# DS2482_Breakout.net
KiCad netlist of a schematic drawn in EAGLE
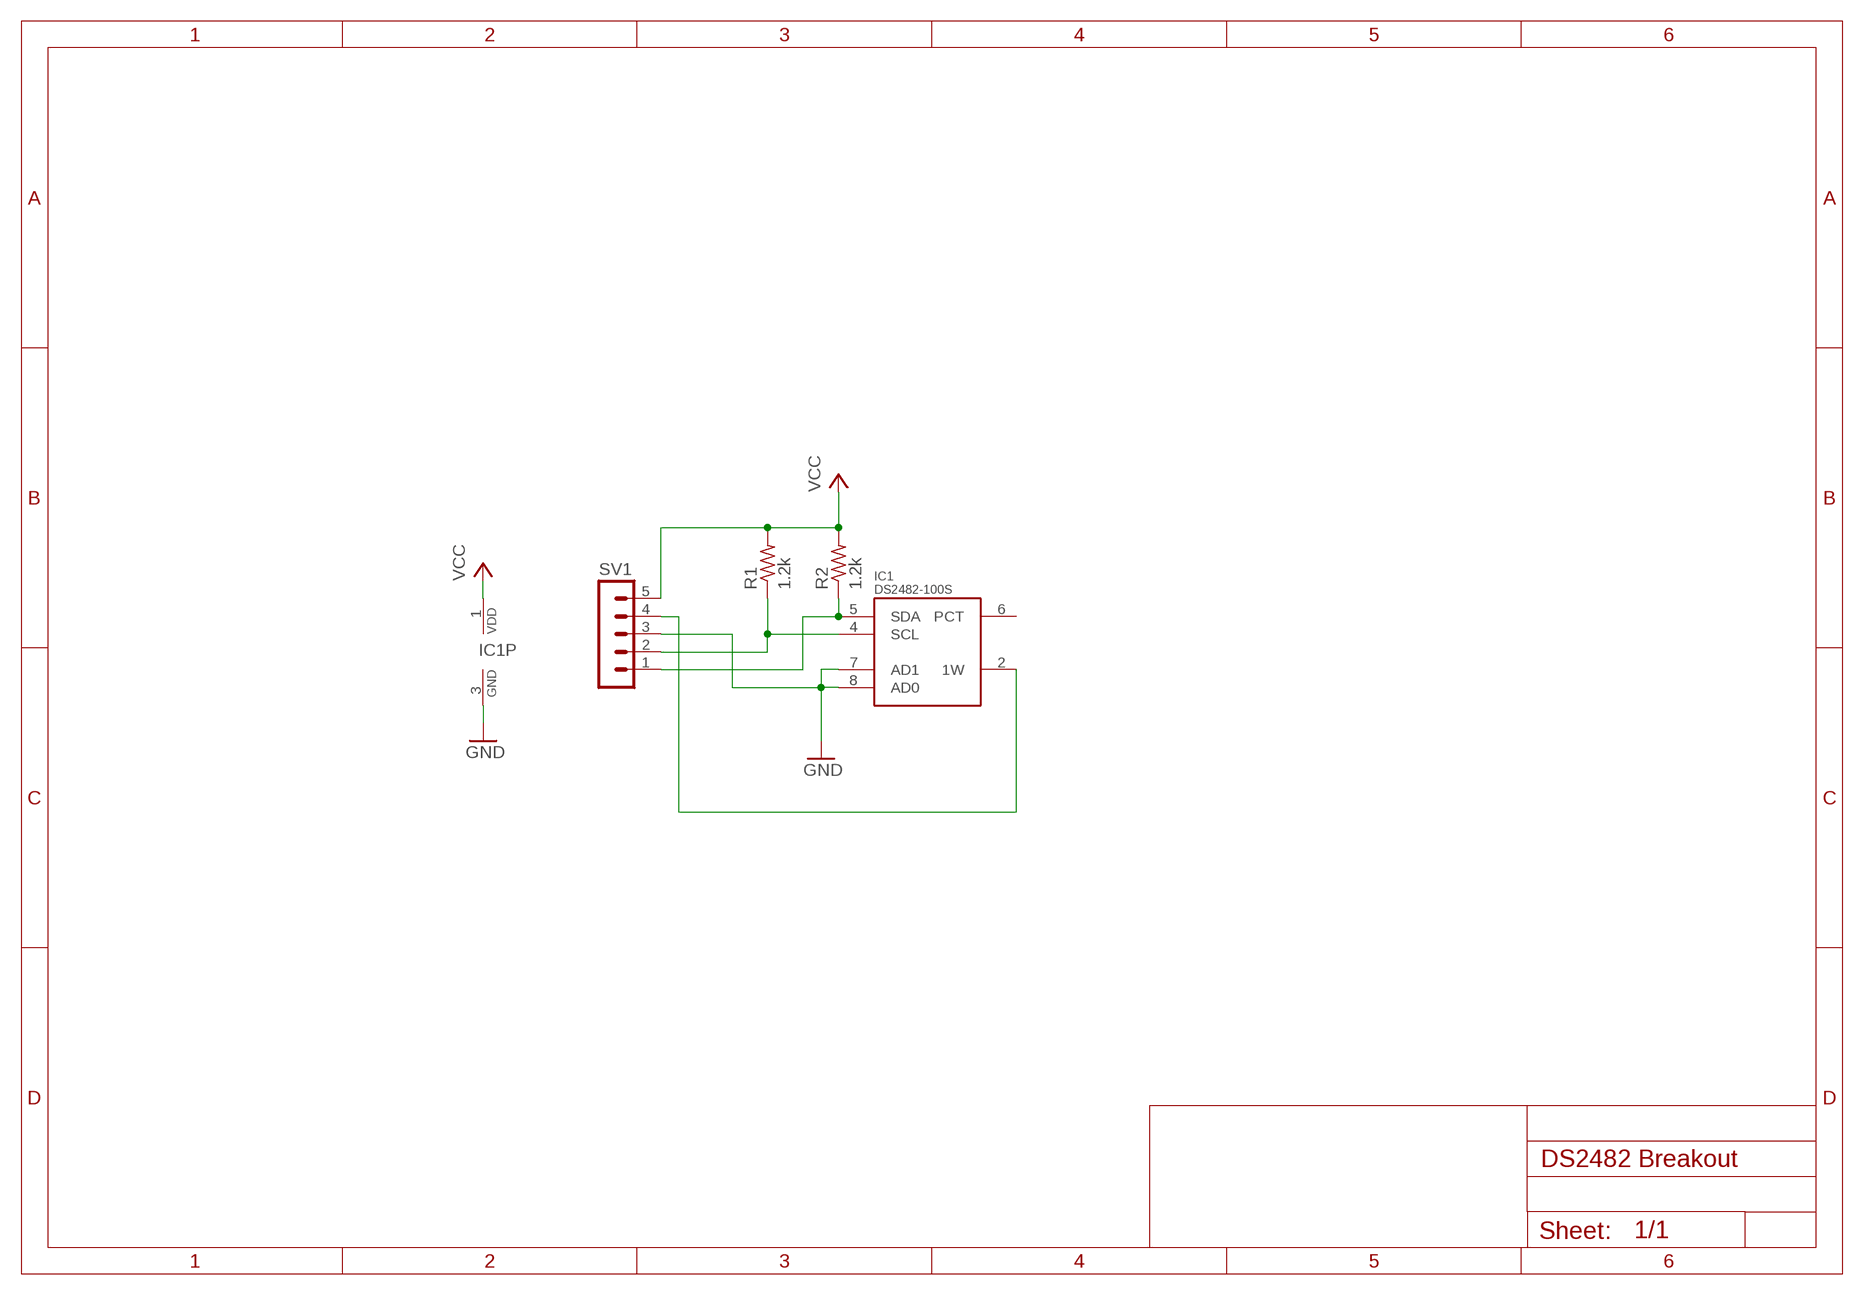
[diagram p0: schematic, sheet 1]

(export (version "E")
  (design (tool "Eeschema 10.0.6"))
  (components
    (comp (ref "IC1")
      (value "DS2482-100S")
      (footprint "eagle-import:SO08")
      (libsource (lib "eagle-import") (part "DS2482-100S"))
    )
    (comp (ref "R1")
      (value "1.2k")
      (footprint "eagle-import:M0805")
      (libsource (lib "eagle-import") (part "R-US_M0805"))
    )
    (comp (ref "R2")
      (value "1.2k")
      (footprint "eagle-import:M0805")
      (libsource (lib "eagle-import") (part "R-US_M0805"))
    )
    (comp (ref "SV1")
      (value "MA05-1")
      (footprint "eagle-import:MA05-1")
      (libsource (lib "eagle-import") (part "MA05-1"))
    )
  )
  (nets
    (net (code "1") (name "GND") (class "Default")
      (node (ref "IC1") (pin "3") (pinfunction "GND_3") (pintype "power_in"))
      (node (ref "IC1") (pin "7") (pinfunction "AD1_7") (pintype "input"))
      (node (ref "IC1") (pin "8") (pinfunction "AD0_8") (pintype "input"))
      (node (ref "SV1") (pin "3") (pinfunction "3_3") (pintype "passive"))
    )
    (net (code "2") (name "Net-(IC1A-1W)") (class "Default")
      (node (ref "IC1") (pin "2") (pinfunction "1W_2") (pintype "open_collector"))
      (node (ref "SV1") (pin "4") (pinfunction "4_4") (pintype "passive"))
    )
    (net (code "3") (name "Net-(IC1A-SCL)") (class "Default")
      (node (ref "IC1") (pin "4") (pinfunction "SCL_4") (pintype "input"))
      (node (ref "R1") (pin "1") (pinfunction "1_1") (pintype "passive"))
      (node (ref "SV1") (pin "2") (pinfunction "2_2") (pintype "passive"))
    )
    (net (code "4") (name "Net-(IC1A-SDA)") (class "Default")
      (node (ref "IC1") (pin "5") (pinfunction "SDA_5") (pintype "bidirectional"))
      (node (ref "R2") (pin "1") (pinfunction "1_1") (pintype "passive"))
      (node (ref "SV1") (pin "1") (pinfunction "1_1") (pintype "passive"))
    )
    (net (code "5") (name "VCC") (class "Default")
      (node (ref "IC1") (pin "1") (pinfunction "VDD_1") (pintype "power_in"))
      (node (ref "R1") (pin "2") (pinfunction "2_2") (pintype "passive"))
      (node (ref "R2") (pin "2") (pinfunction "2_2") (pintype "passive"))
      (node (ref "SV1") (pin "5") (pinfunction "5_5") (pintype "passive"))
    )
    (net (code "6") (name "unconnected-(IC1A-PCT-Pad6)") (class "Default")
      (node (ref "IC1") (pin "6") (pinfunction "PCT_6") (pintype "output"))
    )
  )
)
